# usbasp.net
KiCad netlist of a schematic drawn in Altium Designer
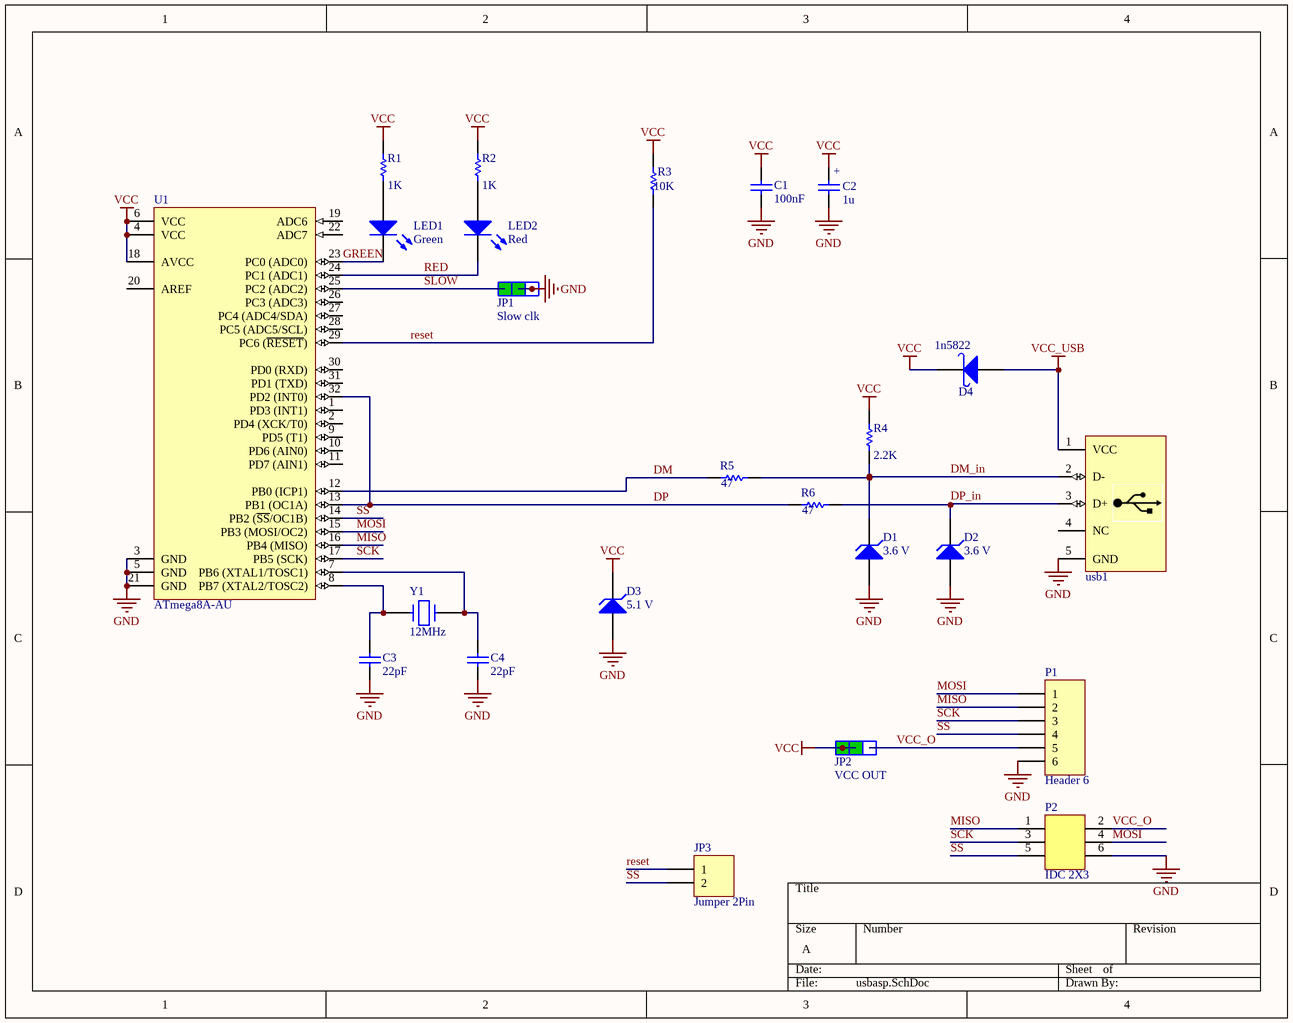
[diagram p0: usbasp.SchDoc]

(export (version "E")
  (design (tool "Eeschema 10.0.6"))
  (components
    (comp (ref "C1")
      (value "100nF")
      (footprint "cap0603")
      (description "=value")
      (fields (field (name "Comment") "Cap"))
      (libsource (lib "Altium library (www.AVRelec.com)") (part "Cap ceramic"))
    )
    (comp (ref "C2")
      (value "1u")
      (footprint "cap0603")
      (description "CAP-3300Uf")
      (fields (field (name "Comment") "Cap"))
      (libsource (lib "Altium library (www.AVRelec.com)") (part "Cap Pol"))
    )
    (comp (ref "C3")
      (value "22pF")
      (footprint "cap0603")
      (description "=value")
      (fields (field (name "Comment") "Cap"))
      (libsource (lib "Altium library (www.AVRelec.com)") (part "Cap ceramic"))
    )
    (comp (ref "C4")
      (value "22pF")
      (footprint "cap0603")
      (description "=value")
      (fields (field (name "Comment") "Cap"))
      (libsource (lib "Altium library (www.AVRelec.com)") (part "Cap ceramic"))
    )
    (comp (ref "D1")
      (value "Diode Zener")
      (footprint "Diode 1n4148 SMD")
      (description "Zener Diode")
      (fields (field (name "VOLTAGE") "3.6 V") (field (name "DESIGNER") "Saeid Jorablo"))
      (libsource (lib "Altium") (part "Diode Zener"))
    )
    (comp (ref "D2")
      (value "Diode Zener")
      (footprint "Diode 1n4148 SMD")
      (description "Zener Diode")
      (fields (field (name "VOLTAGE") "3.6 V") (field (name "DESIGNER") "Saeid Jorablo"))
      (libsource (lib "Altium") (part "Diode Zener"))
    )
    (comp (ref "D3")
      (value "Diode Zener")
      (footprint "Diode 1n4148 SMD")
      (description "Zener Diode")
      (fields (field (name "VOLTAGE") "5.1 V") (field (name "DESIGNER") "Saeid Jorablo"))
      (libsource (lib "Altium") (part "Diode Zener"))
    )
    (comp (ref "D4")
      (value "1n5822")
      (footprint "DO-214AC(SMA)")
      (description "Schottky Rectifiers")
      (fields
        (field (name "MANUFACTURER") "ON Semiconductor/Fairchild")
        (field (name "DESIGNER") "Abbas Basereh")
      )
      (libsource (lib "Altium (2)") (part "1N5822 SMD"))
    )
    (comp (ref "JP1")
      (value "Slow clk")
      (footprint "jumper selector")
      (description "Jumper Selector")
      (libsource (lib "Altium (2)") (part "Jumper Selector"))
    )
    (comp (ref "JP2")
      (value "VCC OUT")
      (footprint "jumper selector")
      (description "Jumper Selector")
      (libsource (lib "Altium (2)") (part "Jumper Selector"))
    )
    (comp (ref "JP3")
      (value "Jumper 2Pin")
      (footprint "PCBComponent_1")
      (description "Jumper, 2-Pin")
      (fields (field (name "DESIGNER") "Abbas Basereh"))
      (libsource (lib "Altium (2)") (part "Jumper 2Pin"))
    )
    (comp (ref "LED1")
      (value "Green")
      (footprint "LED_0603 G")
      (description "Typical INFRARED GaAs LED")
      (fields (field (name "PUBLISHER") "Altium Limited"))
      (libsource (lib "Miscellaneous Devices") (part "LED0"))
    )
    (comp (ref "LED2")
      (value "Red")
      (footprint "LED_0603 R")
      (description "Typical INFRARED GaAs LED")
      (fields (field (name "PUBLISHER") "Altium Limited"))
      (libsource (lib "Miscellaneous Devices") (part "LED0"))
    )
    (comp (ref "P1")
      (value "Header 6")
      (footprint "HDR1X6")
      (description "Header, 6-Pin")
      (fields (field (name "PUBLISHER") "Altium Limited"))
      (libsource (lib "Miscellaneous Connectors") (part "Header 6"))
    )
    (comp (ref "P2")
      (value "IDC 2X3")
      (footprint "IDC Socket Male 6pin Straight THT Goldplated 2_54mm")
      (libsource (lib "ZetaBoard_Lib") (part "IDC 2X3"))
    )
    (comp (ref "R1")
      (value "1K")
      (footprint "RES0603")
      (description "Resistor")
      (fields (field (name "PUBLISHER") "Altium Limited"))
      (libsource (lib "Miscellaneous Devices") (part "Res1"))
    )
    (comp (ref "R2")
      (value "1K")
      (footprint "RES0603")
      (description "Resistor")
      (fields (field (name "PUBLISHER") "Altium Limited"))
      (libsource (lib "Miscellaneous Devices") (part "Res1"))
    )
    (comp (ref "R3")
      (value "10K")
      (footprint "RES0603")
      (description "Resistor")
      (fields (field (name "PUBLISHER") "Altium Limited"))
      (libsource (lib "Miscellaneous Devices") (part "Res1"))
    )
    (comp (ref "R4")
      (value "2.2K")
      (footprint "RES0603")
      (description "Resistor")
      (fields (field (name "PUBLISHER") "Altium Limited"))
      (libsource (lib "Miscellaneous Devices") (part "Res1"))
    )
    (comp (ref "R5")
      (value "47")
      (footprint "RES0603")
      (description "Resistor")
      (fields (field (name "PUBLISHER") "Altium Limited"))
      (libsource (lib "Miscellaneous Devices") (part "Res1"))
    )
    (comp (ref "R6")
      (value "47")
      (footprint "RES0603")
      (description "Resistor")
      (fields (field (name "PUBLISHER") "Altium Limited"))
      (libsource (lib "Miscellaneous Devices") (part "Res1"))
    )
    (comp (ref "U1")
      (value "ATmega8A-AU")
      (footprint "TQFP32_N")
      (fields (field (name "PUBLISHER") "Altium Limited"))
      (libsource (lib "Altium (2)") (part "ATmega8A-AU"))
    )
    (comp (ref "usb1")
      (value "USB Connector")
      (footprint "USB_AB_BM_SHS")
      (description "USB Connector MICRO-B Type")
      (fields (field (name "DESIGNER") "ABBAS BASEREH") (field (name "PUBLISHER") "ABBAS BASEREH"))
      (libsource (lib "Altium (2)") (part "USB MICRO"))
    )
    (comp (ref "Y1")
      (value "12MHz")
      (footprint "CRYSTAL Small")
      (description "Crystal")
      (libsource (lib "Altium library (www.AVRelec.com)") (part "CRYSTAL"))
    )
  )
  (nets
    (net (code "1") (name "/DM") (class "Default")
      (node (ref "R5") (pin "1") (pinfunction "1_1") (pintype "passive"))
      (node (ref "U1") (pin "12") (pinfunction "PB0_(ICP1)_12") (pintype "bidirectional"))
    )
    (net (code "2") (name "/DM_in") (class "Default")
      (node (ref "D1") (pin "2") (pinfunction "K_2") (pintype "passive"))
      (node (ref "R4") (pin "1") (pinfunction "1_1") (pintype "passive"))
      (node (ref "R5") (pin "2") (pinfunction "2_2") (pintype "passive"))
      (node (ref "usb1") (pin "2") (pinfunction "D-_2") (pintype "bidirectional"))
    )
    (net (code "3") (name "/DP") (class "Default")
      (node (ref "R6") (pin "1") (pinfunction "1_1") (pintype "passive"))
      (node (ref "U1") (pin "13") (pinfunction "PB1_(OC1A)_13") (pintype "bidirectional"))
      (node (ref "U1") (pin "32") (pinfunction "PD2_(INT0)_32") (pintype "bidirectional"))
    )
    (net (code "4") (name "/DP_in") (class "Default")
      (node (ref "D2") (pin "2") (pinfunction "K_2") (pintype "passive"))
      (node (ref "R6") (pin "2") (pinfunction "2_2") (pintype "passive"))
      (node (ref "usb1") (pin "3") (pinfunction "D+_3") (pintype "bidirectional"))
    )
    (net (code "5") (name "/GREEN") (class "Default")
      (node (ref "LED1") (pin "2") (pinfunction "K_2") (pintype "passive"))
      (node (ref "U1") (pin "23") (pinfunction "PC0_(ADC0)_23") (pintype "bidirectional"))
    )
    (net (code "6") (name "/MISO") (class "Default")
      (node (ref "P1") (pin "2") (pinfunction "2_2") (pintype "passive"))
      (node (ref "P2") (pin "1") (pinfunction "1_1") (pintype "passive"))
      (node (ref "U1") (pin "16") (pinfunction "PB4_(MISO)_16") (pintype "bidirectional"))
    )
    (net (code "7") (name "/MOSI") (class "Default")
      (node (ref "P1") (pin "1") (pinfunction "1_1") (pintype "passive"))
      (node (ref "P2") (pin "4") (pinfunction "4_4") (pintype "passive"))
      (node (ref "U1") (pin "15") (pinfunction "PB3_(MOSI/OC2)_15") (pintype "bidirectional"))
    )
    (net (code "8") (name "/RED") (class "Default")
      (node (ref "LED2") (pin "2") (pinfunction "K_2") (pintype "passive"))
      (node (ref "U1") (pin "24") (pinfunction "PC1_(ADC1)_24") (pintype "bidirectional"))
    )
    (net (code "9") (name "/SCK") (class "Default")
      (node (ref "P1") (pin "3") (pinfunction "3_3") (pintype "passive"))
      (node (ref "P2") (pin "3") (pinfunction "3_3") (pintype "passive"))
      (node (ref "U1") (pin "17") (pinfunction "PB5_(SCK)_17") (pintype "bidirectional"))
    )
    (net (code "10") (name "/SLOW") (class "Default")
      (node (ref "JP1") (pin "1") (pinfunction "1_1") (pintype "passive"))
      (node (ref "U1") (pin "25") (pinfunction "PC2_(ADC2)_25") (pintype "bidirectional"))
    )
    (net (code "11") (name "/SS") (class "Default")
      (node (ref "JP3") (pin "2") (pinfunction "2_2") (pintype "passive"))
      (node (ref "P1") (pin "4") (pinfunction "4_4") (pintype "passive"))
      (node (ref "P2") (pin "5") (pinfunction "5_5") (pintype "passive"))
      (node (ref "U1") (pin "14") (pinfunction "PB2_(~{SS}/OC1B)_14") (pintype "bidirectional"))
    )
    (net (code "12") (name "/VCC_O") (class "Default")
      (node (ref "JP2") (pin "3") (pinfunction "3_3") (pintype "passive"))
      (node (ref "P1") (pin "5") (pinfunction "5_5") (pintype "passive"))
      (node (ref "P2") (pin "2") (pinfunction "2_2") (pintype "passive"))
    )
    (net (code "13") (name "/reset") (class "Default")
      (node (ref "JP3") (pin "1") (pinfunction "1_1") (pintype "passive"))
      (node (ref "R3") (pin "1") (pinfunction "1_1") (pintype "passive"))
      (node (ref "U1") (pin "29") (pinfunction "PC6_(~{RESET})_29") (pintype "bidirectional"))
    )
    (net (code "14") (name "GND") (class "Default")
      (node (ref "C1") (pin "1") (pinfunction "1_1") (pintype "passive"))
      (node (ref "C2") (pin "-") (pinfunction "-_-") (pintype "passive"))
      (node (ref "C3") (pin "1") (pinfunction "1_1") (pintype "passive"))
      (node (ref "C4") (pin "1") (pinfunction "1_1") (pintype "passive"))
      (node (ref "D1") (pin "1") (pinfunction "A_1") (pintype "passive"))
      (node (ref "D2") (pin "1") (pinfunction "A_1") (pintype "passive"))
      (node (ref "D3") (pin "1") (pinfunction "A_1") (pintype "passive"))
      (node (ref "JP1") (pin "2") (pinfunction "2_2") (pintype "passive"))
      (node (ref "JP1") (pin "3") (pinfunction "3_3") (pintype "passive"))
      (node (ref "P1") (pin "6") (pinfunction "6_6") (pintype "passive"))
      (node (ref "P2") (pin "6") (pinfunction "6_6") (pintype "passive"))
      (node (ref "U1") (pin "21") (pinfunction "GND_21") (pintype "power_in"))
      (node (ref "U1") (pin "3") (pinfunction "GND_3") (pintype "power_in"))
      (node (ref "U1") (pin "5") (pinfunction "GND_5") (pintype "power_in"))
      (node (ref "usb1") (pin "5") (pinfunction "GND_5") (pintype "power_in"))
    )
    (net (code "15") (name "Net-(LED1-A)") (class "Default")
      (node (ref "LED1") (pin "1") (pinfunction "A_1") (pintype "passive"))
      (node (ref "R1") (pin "1") (pinfunction "1_1") (pintype "passive"))
    )
    (net (code "16") (name "Net-(LED2-A)") (class "Default")
      (node (ref "LED2") (pin "1") (pinfunction "A_1") (pintype "passive"))
      (node (ref "R2") (pin "1") (pinfunction "1_1") (pintype "passive"))
    )
    (net (code "17") (name "Net-(U1-PB6_(XTAL1{slash}TOSC1))") (class "Default")
      (node (ref "C4") (pin "2") (pinfunction "2_2") (pintype "passive"))
      (node (ref "U1") (pin "7") (pinfunction "PB6_(XTAL1/TOSC1)_7") (pintype "bidirectional"))
      (node (ref "Y1") (pin "1") (pinfunction "1_1") (pintype "passive"))
    )
    (net (code "18") (name "Net-(U1-PB7_(XTAL2{slash}TOSC2))") (class "Default")
      (node (ref "C3") (pin "2") (pinfunction "2_2") (pintype "passive"))
      (node (ref "U1") (pin "8") (pinfunction "PB7_(XTAL2/TOSC2)_8") (pintype "bidirectional"))
      (node (ref "Y1") (pin "2") (pinfunction "2_2") (pintype "passive"))
    )
    (net (code "19") (name "VCC") (class "Default")
      (node (ref "C1") (pin "2") (pinfunction "2_2") (pintype "passive"))
      (node (ref "C2") (pin "+") (pinfunction "+_+") (pintype "passive"))
      (node (ref "D3") (pin "2") (pinfunction "K_2") (pintype "passive"))
      (node (ref "D4") (pin "2") (pinfunction "K_2") (pintype "passive"))
      (node (ref "JP2") (pin "1") (pinfunction "1_1") (pintype "passive"))
      (node (ref "JP2") (pin "2") (pinfunction "2_2") (pintype "passive"))
      (node (ref "R1") (pin "2") (pinfunction "2_2") (pintype "passive"))
      (node (ref "R2") (pin "2") (pinfunction "2_2") (pintype "passive"))
      (node (ref "R3") (pin "2") (pinfunction "2_2") (pintype "passive"))
      (node (ref "R4") (pin "2") (pinfunction "2_2") (pintype "passive"))
      (node (ref "U1") (pin "18") (pinfunction "AVCC_18") (pintype "power_in"))
      (node (ref "U1") (pin "4") (pinfunction "VCC_4") (pintype "power_in"))
      (node (ref "U1") (pin "6") (pinfunction "VCC_6") (pintype "power_in"))
    )
    (net (code "20") (name "VCC_USB") (class "Default")
      (node (ref "D4") (pin "1") (pinfunction "A_1") (pintype "passive"))
      (node (ref "usb1") (pin "1") (pinfunction "VCC_1") (pintype "power_in"))
    )
    (net (code "21") (name "unconnected-(U1-ADC6-Pad19)") (class "Default")
      (node (ref "U1") (pin "19") (pinfunction "ADC6_19") (pintype "input"))
    )
    (net (code "22") (name "unconnected-(U1-ADC7-Pad22)") (class "Default")
      (node (ref "U1") (pin "22") (pinfunction "ADC7_22") (pintype "input"))
    )
    (net (code "23") (name "unconnected-(U1-AREF-Pad20)") (class "Default")
      (node (ref "U1") (pin "20") (pinfunction "AREF_20") (pintype "power_in"))
    )
    (net (code "24") (name "unconnected-(U1-PC3_(ADC3)-Pad26)") (class "Default")
      (node (ref "U1") (pin "26") (pinfunction "PC3_(ADC3)_26") (pintype "bidirectional"))
    )
    (net (code "25") (name "unconnected-(U1-PC4_(ADC4{slash}SDA)-Pad27)") (class "Default")
      (node (ref "U1") (pin "27") (pinfunction "PC4_(ADC4/SDA)_27") (pintype "bidirectional"))
    )
    (net (code "26") (name "unconnected-(U1-PC5_(ADC5{slash}SCL)-Pad28)") (class "Default")
      (node (ref "U1") (pin "28") (pinfunction "PC5_(ADC5/SCL)_28") (pintype "bidirectional"))
    )
    (net (code "27") (name "unconnected-(U1-PD0_(RXD)-Pad30)") (class "Default")
      (node (ref "U1") (pin "30") (pinfunction "PD0_(RXD)_30") (pintype "bidirectional"))
    )
    (net (code "28") (name "unconnected-(U1-PD1_(TXD)-Pad31)") (class "Default")
      (node (ref "U1") (pin "31") (pinfunction "PD1_(TXD)_31") (pintype "bidirectional"))
    )
    (net (code "29") (name "unconnected-(U1-PD3_(INT1)-Pad1)") (class "Default")
      (node (ref "U1") (pin "1") (pinfunction "PD3_(INT1)_1") (pintype "bidirectional"))
    )
    (net (code "30") (name "unconnected-(U1-PD4_(XCK{slash}T0)-Pad2)") (class "Default")
      (node (ref "U1") (pin "2") (pinfunction "PD4_(XCK/T0)_2") (pintype "bidirectional"))
    )
    (net (code "31") (name "unconnected-(U1-PD5_(T1)-Pad9)") (class "Default")
      (node (ref "U1") (pin "9") (pinfunction "PD5_(T1)_9") (pintype "bidirectional"))
    )
    (net (code "32") (name "unconnected-(U1-PD6_(AIN0)-Pad10)") (class "Default")
      (node (ref "U1") (pin "10") (pinfunction "PD6_(AIN0)_10") (pintype "bidirectional"))
    )
    (net (code "33") (name "unconnected-(U1-PD7_(AIN1)-Pad11)") (class "Default")
      (node (ref "U1") (pin "11") (pinfunction "PD7_(AIN1)_11") (pintype "bidirectional"))
    )
    (net (code "34") (name "unconnected-(usb1-NC-Pad4)") (class "Default")
      (node (ref "usb1") (pin "4") (pinfunction "NC_4") (pintype "passive"))
    )
  )
)
